# Driver_SCR.net
KiCad netlist of a schematic drawn in Altium Designer
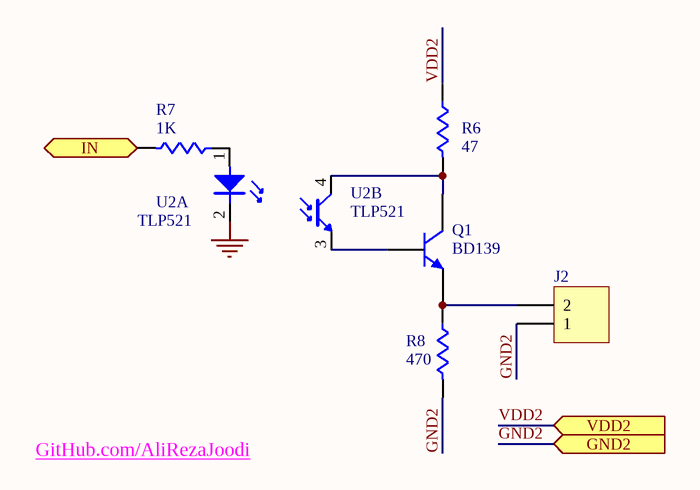
[diagram p0: Driver_SCR.SchDoc]

(export (version "E")
  (design (tool "Eeschema 10.0.6"))
  (components
    (comp (ref "J2")
      (value "J2")
      (footprint "Fonics_2PIN_1")
      (description "Header, 2-Pin")
      (fields (field (name "PUBLISHER") "Altium Limited"))
      (libsource (lib "Miscellaneous Connectors") (part "Header 2"))
    )
    (comp (ref "Q1")
      (value "Q1")
      (footprint "SOT-32")
      (description "NPN Transistor")
      (fields (field (name "ALTIUM_VALUE") "BD139") (field (name "E-MAIL") "picpars@gmail.com"))
      (libsource (lib "PicPars.com_usefully_Library") (part "BD139"))
    )
    (comp (ref "R6")
      (value "47")
      (footprint "AXIAL-0.4")
      (description "Resistor")
      (fields
        (field (name "MANUFACTURER") "Generic Components")
        (field (name "Comment") "R6")
        (field (name "PUBLISHER") "Altium Limited")
      )
      (libsource (lib "Miscellaneous Devices") (part "Res1"))
    )
    (comp (ref "R7")
      (value "1K")
      (footprint "AXIAL-0.4")
      (description "Resistor")
      (fields
        (field (name "MANUFACTURER") "Generic Components")
        (field (name "Comment") "R7")
        (field (name "PUBLISHER") "Altium Limited")
      )
      (libsource (lib "Miscellaneous Devices") (part "Res1"))
    )
    (comp (ref "R8")
      (value "470")
      (footprint "AXIAL-0.4")
      (description "Resistor")
      (fields
        (field (name "MANUFACTURER") "Generic Components")
        (field (name "Comment") "R8")
        (field (name "PUBLISHER") "Altium Limited")
      )
      (libsource (lib "Miscellaneous Devices") (part "Res1"))
    )
    (comp (ref "U2")
      (value "TLP521")
      (footprint "DIP-4")
      (fields (field (name "Comment") "U2") (field (name "PUBLISHER") "Altium Limited"))
      (libsource (lib "my Libraries") (part "Optoisolator"))
    )
  )
  (nets
    (net (code "1") (name "/GND2") (class "Default")
      (node (ref "J2") (pin "1") (pinfunction "1_1") (pintype "passive"))
      (node (ref "R8") (pin "2") (pinfunction "2_2") (pintype "passive"))
    )
    (net (code "2") (name "/IN") (class "Default")
      (node (ref "R7") (pin "2") (pinfunction "2_2") (pintype "passive"))
    )
    (net (code "3") (name "/VDD2") (class "Default")
      (node (ref "R6") (pin "1") (pinfunction "1_1") (pintype "passive"))
    )
    (net (code "4") (name "GND") (class "Default")
      (node (ref "U2") (pin "2") (pinfunction "K_2") (pintype "power_in"))
    )
    (net (code "5") (name "Net-(J2-Pad2)") (class "Default")
      (node (ref "J2") (pin "2") (pinfunction "2_2") (pintype "passive"))
      (node (ref "Q1") (pin "E") (pinfunction "E_E") (pintype "passive"))
      (node (ref "R8") (pin "1") (pinfunction "1_1") (pintype "passive"))
    )
    (net (code "6") (name "Net-(U2A-A)") (class "Default")
      (node (ref "R7") (pin "1") (pinfunction "1_1") (pintype "passive"))
      (node (ref "U2") (pin "1") (pinfunction "A_1") (pintype "power_in"))
    )
    (net (code "7") (name "Net-(U2B-C)") (class "Default")
      (node (ref "Q1") (pin "C") (pinfunction "C_C") (pintype "passive"))
      (node (ref "R6") (pin "2") (pinfunction "2_2") (pintype "passive"))
      (node (ref "U2") (pin "4") (pinfunction "C_4") (pintype "passive"))
    )
    (net (code "8") (name "Net-(U2B-E)") (class "Default")
      (node (ref "Q1") (pin "B") (pinfunction "B_B") (pintype "passive"))
      (node (ref "U2") (pin "3") (pinfunction "E_3") (pintype "passive"))
    )
  )
)
